# schematic.net
KiCad netlist of a schematic drawn in EasyEDA Pro
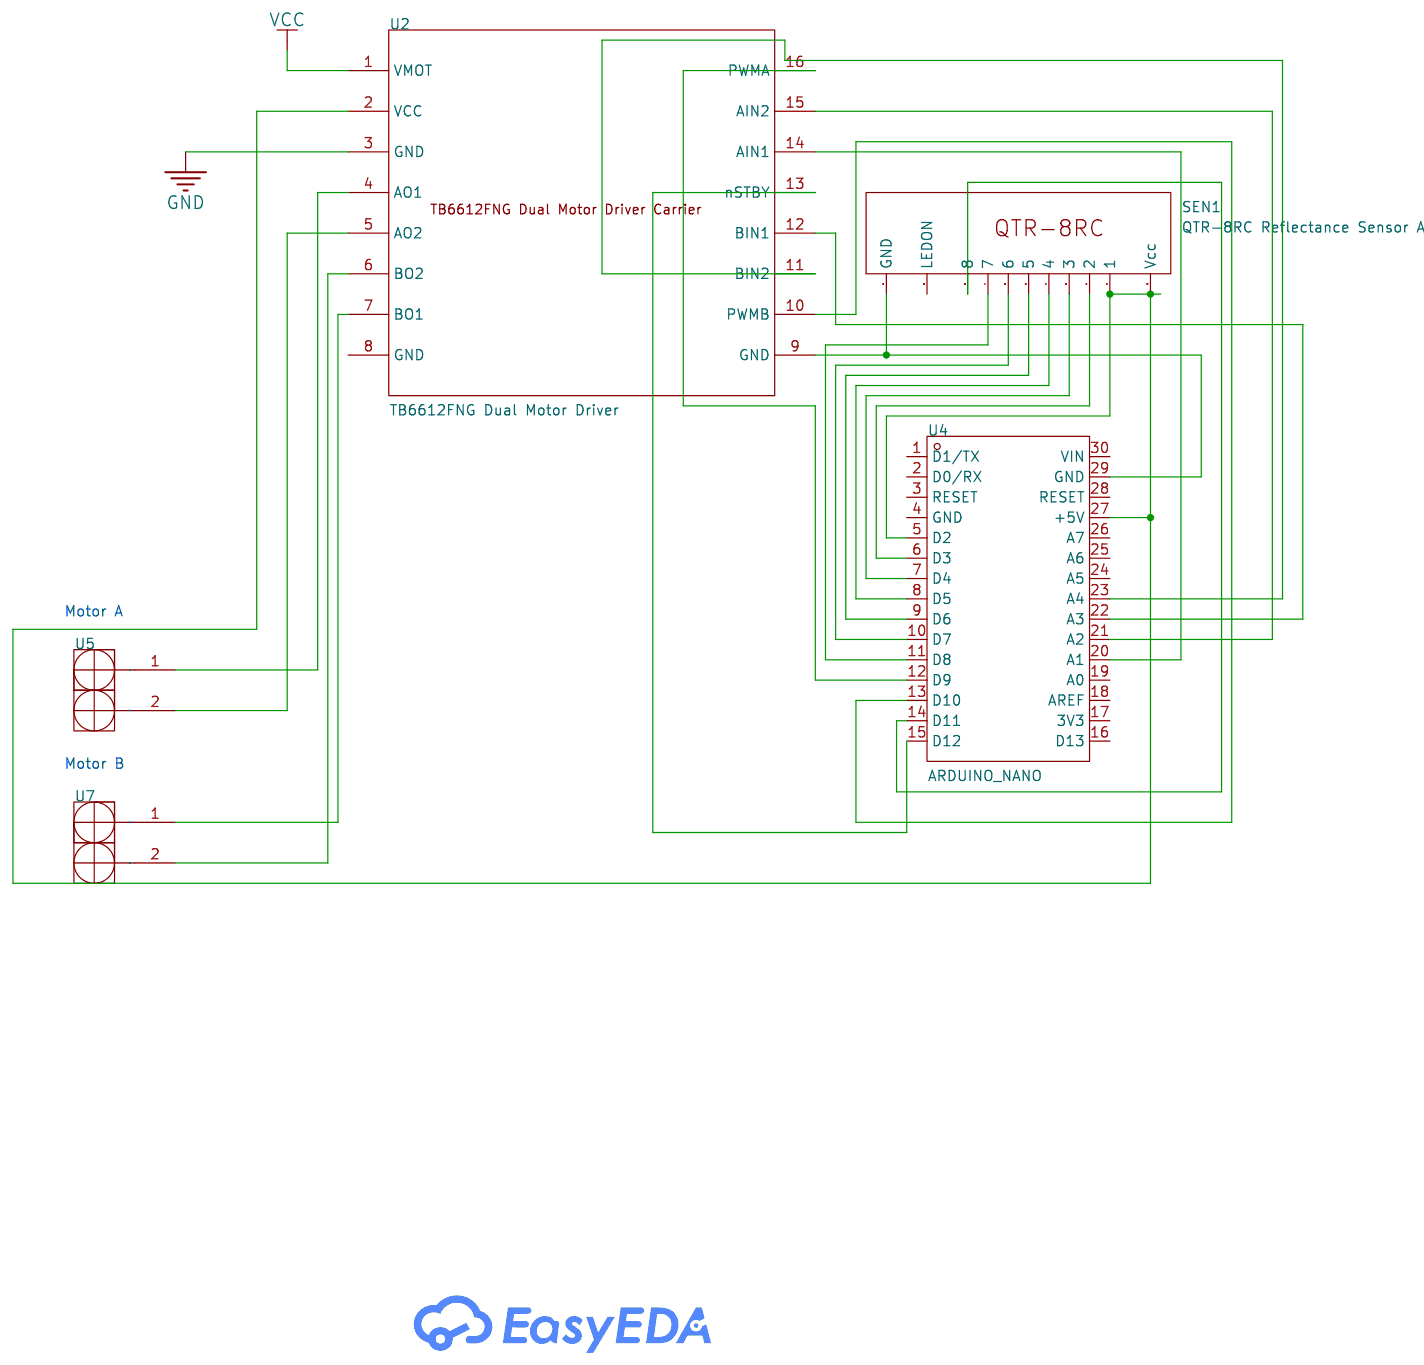
[diagram p0: schematic sheet]

(export (version "E")
  (design (tool "Eeschema 10.0.6"))
  (components
    (comp (ref "SEN1")
      (value "QTR-8RC Reflectance Sensor Array")
      (footprint "easyedapro:QTR-8X")
      (fields (field (name "Manufacturer") "Pololu"))
      (libsource (lib "easyedapro") (part "QTR-8RC Reflectance Sensor Array"))
    )
    (comp (ref "U2")
      (value "TB6612FNG Dual Motor Driver")
      (footprint "easyedapro:TB6612FNG")
      (libsource (lib "easyedapro") (part "TB6612FNG Dual Motor Driver"))
    )
    (comp (ref "U4")
      (value "ARDUINO_NANO")
      (footprint "easyedapro:COMM-TH_ARDUINO_NANO")
      (libsource (lib "easyedapro") (part "ARDUINO_NANO"))
    )
    (comp (ref "U5")
      (value "~")
      (footprint "easyedapro:2PIN SCREW TERMINAL")
      (libsource (lib "easyedapro") (part "2PIN SCREW TERMINAL"))
    )
    (comp (ref "U7")
      (value "~")
      (footprint "easyedapro:2PIN SCREW TERMINAL")
      (libsource (lib "easyedapro") (part "2PIN SCREW TERMINAL"))
    )
  )
  (nets
    (net (code "1") (name "GND") (class "Default")
      (node (ref "U2") (pin "3") (pinfunction "GND_3") (pintype "unspecified"))
    )
    (net (code "2") (name "Net-(SEN1-GND)") (class "Default")
      (node (ref "SEN1") (pin "11") (pinfunction "GND_11") (pintype "unspecified"))
      (node (ref "U2") (pin "9") (pinfunction "GND_9") (pintype "unspecified"))
      (node (ref "U4") (pin "29") (pinfunction "GND_29") (pintype "unspecified"))
    )
    (net (code "3") (name "Net-(SEN1-Vcc)") (class "Default")
      (node (ref "SEN1") (pin "1") (pinfunction "1_1") (pintype "unspecified"))
      (node (ref "SEN1") (pin "10") (pinfunction "Vcc_10") (pintype "unspecified"))
      (node (ref "U2") (pin "2") (pinfunction "VCC_2") (pintype "unspecified"))
      (node (ref "U4") (pin "27") (pinfunction "+5V_27") (pintype "unspecified"))
      (node (ref "U4") (pin "5") (pinfunction "D2_5") (pintype "unspecified"))
    )
    (net (code "4") (name "Net-(U2-AIN1)") (class "Default")
      (node (ref "U2") (pin "14") (pinfunction "AIN1_14") (pintype "unspecified"))
      (node (ref "U4") (pin "20") (pinfunction "A1_20") (pintype "unspecified"))
    )
    (net (code "5") (name "Net-(U2-AIN2)") (class "Default")
      (node (ref "U2") (pin "15") (pinfunction "AIN2_15") (pintype "unspecified"))
      (node (ref "U4") (pin "21") (pinfunction "A2_21") (pintype "unspecified"))
    )
    (net (code "6") (name "Net-(U2-AO1)") (class "Default")
      (node (ref "U2") (pin "4") (pinfunction "AO1_4") (pintype "unspecified"))
      (node (ref "U5") (pin "1") (pinfunction "1_1") (pintype "input"))
    )
    (net (code "7") (name "Net-(U2-AO2)") (class "Default")
      (node (ref "U2") (pin "5") (pinfunction "AO2_5") (pintype "unspecified"))
      (node (ref "U5") (pin "2") (pinfunction "2_2") (pintype "input"))
    )
    (net (code "8") (name "Net-(U2-BIN1)") (class "Default")
      (node (ref "U2") (pin "12") (pinfunction "BIN1_12") (pintype "unspecified"))
      (node (ref "U4") (pin "22") (pinfunction "A3_22") (pintype "unspecified"))
    )
    (net (code "9") (name "Net-(U2-BIN2)") (class "Default")
      (node (ref "U2") (pin "11") (pinfunction "BIN2_11") (pintype "unspecified"))
      (node (ref "U4") (pin "23") (pinfunction "A4_23") (pintype "unspecified"))
    )
    (net (code "10") (name "Net-(U2-BO1)") (class "Default")
      (node (ref "U2") (pin "7") (pinfunction "BO1_7") (pintype "unspecified"))
      (node (ref "U7") (pin "1") (pinfunction "1_1") (pintype "input"))
    )
    (net (code "11") (name "Net-(U2-BO2)") (class "Default")
      (node (ref "U2") (pin "6") (pinfunction "BO2_6") (pintype "unspecified"))
      (node (ref "U7") (pin "2") (pinfunction "2_2") (pintype "input"))
    )
    (net (code "12") (name "Net-(U2-PWMA)") (class "Default")
      (node (ref "U2") (pin "16") (pinfunction "PWMA_16") (pintype "unspecified"))
      (node (ref "U4") (pin "12") (pinfunction "D9_12") (pintype "unspecified"))
    )
    (net (code "13") (name "Net-(U2-PWMB)") (class "Default")
      (node (ref "U2") (pin "10") (pinfunction "PWMB_10") (pintype "unspecified"))
      (node (ref "U4") (pin "13") (pinfunction "D10_13") (pintype "unspecified"))
    )
    (net (code "14") (name "Net-(U2-nSTBY)") (class "Default")
      (node (ref "U2") (pin "13") (pinfunction "nSTBY_13") (pintype "unspecified"))
      (node (ref "U4") (pin "15") (pinfunction "D12_15") (pintype "unspecified"))
    )
    (net (code "15") (name "Net-(U4-D3)") (class "Default")
      (node (ref "SEN1") (pin "2") (pinfunction "2_2") (pintype "unspecified"))
      (node (ref "U4") (pin "6") (pinfunction "D3_6") (pintype "unspecified"))
    )
    (net (code "16") (name "Net-(U4-D4)") (class "Default")
      (node (ref "SEN1") (pin "3") (pinfunction "3_3") (pintype "unspecified"))
      (node (ref "U4") (pin "7") (pinfunction "D4_7") (pintype "unspecified"))
    )
    (net (code "17") (name "Net-(U4-D5)") (class "Default")
      (node (ref "SEN1") (pin "4") (pinfunction "4_4") (pintype "unspecified"))
      (node (ref "U4") (pin "8") (pinfunction "D5_8") (pintype "unspecified"))
    )
    (net (code "18") (name "Net-(U4-D6)") (class "Default")
      (node (ref "SEN1") (pin "5") (pinfunction "5_5") (pintype "unspecified"))
      (node (ref "U4") (pin "9") (pinfunction "D6_9") (pintype "unspecified"))
    )
    (net (code "19") (name "Net-(U4-D7)") (class "Default")
      (node (ref "SEN1") (pin "6") (pinfunction "6_6") (pintype "unspecified"))
      (node (ref "U4") (pin "10") (pinfunction "D7_10") (pintype "unspecified"))
    )
    (net (code "20") (name "Net-(U4-D8)") (class "Default")
      (node (ref "SEN1") (pin "7") (pinfunction "7_7") (pintype "unspecified"))
      (node (ref "U4") (pin "11") (pinfunction "D8_11") (pintype "unspecified"))
    )
    (net (code "21") (name "Net-(U4-D11)") (class "Default")
      (node (ref "SEN1") (pin "8") (pinfunction "8_8") (pintype "unspecified"))
      (node (ref "U4") (pin "14") (pinfunction "D11_14") (pintype "unspecified"))
    )
    (net (code "22") (name "VCC") (class "Default")
      (node (ref "U2") (pin "1") (pinfunction "VMOT_1") (pintype "unspecified"))
    )
    (net (code "23") (name "unconnected-(SEN1-LEDON-Pad9)") (class "Default")
      (node (ref "SEN1") (pin "9") (pinfunction "LEDON_9") (pintype "unspecified"))
    )
    (net (code "24") (name "unconnected-(U2-GND-Pad8)") (class "Default")
      (node (ref "U2") (pin "8") (pinfunction "GND_8") (pintype "unspecified"))
    )
    (net (code "25") (name "unconnected-(U4-3V3-Pad17)") (class "Default")
      (node (ref "U4") (pin "17") (pinfunction "3V3_17") (pintype "unspecified"))
    )
    (net (code "26") (name "unconnected-(U4-A0-Pad19)") (class "Default")
      (node (ref "U4") (pin "19") (pinfunction "A0_19") (pintype "unspecified"))
    )
    (net (code "27") (name "unconnected-(U4-A5-Pad24)") (class "Default")
      (node (ref "U4") (pin "24") (pinfunction "A5_24") (pintype "unspecified"))
    )
    (net (code "28") (name "unconnected-(U4-A6-Pad25)") (class "Default")
      (node (ref "U4") (pin "25") (pinfunction "A6_25") (pintype "unspecified"))
    )
    (net (code "29") (name "unconnected-(U4-A7-Pad26)") (class "Default")
      (node (ref "U4") (pin "26") (pinfunction "A7_26") (pintype "unspecified"))
    )
    (net (code "30") (name "unconnected-(U4-AREF-Pad18)") (class "Default")
      (node (ref "U4") (pin "18") (pinfunction "AREF_18") (pintype "unspecified"))
    )
    (net (code "31") (name "unconnected-(U4-D0{slash}RX-Pad2)") (class "Default")
      (node (ref "U4") (pin "2") (pinfunction "D0/RX_2") (pintype "unspecified"))
    )
    (net (code "32") (name "unconnected-(U4-D1{slash}TX-Pad1)") (class "Default")
      (node (ref "U4") (pin "1") (pinfunction "D1/TX_1") (pintype "unspecified"))
    )
    (net (code "33") (name "unconnected-(U4-D13-Pad16)") (class "Default")
      (node (ref "U4") (pin "16") (pinfunction "D13_16") (pintype "unspecified"))
    )
    (net (code "34") (name "unconnected-(U4-GND-Pad4)") (class "Default")
      (node (ref "U4") (pin "4") (pinfunction "GND_4") (pintype "unspecified"))
    )
    (net (code "35") (name "unconnected-(U4-RESET-Pad3)") (class "Default")
      (node (ref "U4") (pin "3") (pinfunction "RESET_3") (pintype "unspecified"))
    )
    (net (code "36") (name "unconnected-(U4-RESET-Pad28)") (class "Default")
      (node (ref "U4") (pin "28") (pinfunction "RESET_28") (pintype "unspecified"))
    )
    (net (code "37") (name "unconnected-(U4-VIN-Pad30)") (class "Default")
      (node (ref "U4") (pin "30") (pinfunction "VIN_30") (pintype "unspecified"))
    )
  )
)
